# SCH_Small-keyboard_2024-08-15.net
KiCad netlist of a schematic drawn in EasyEDA
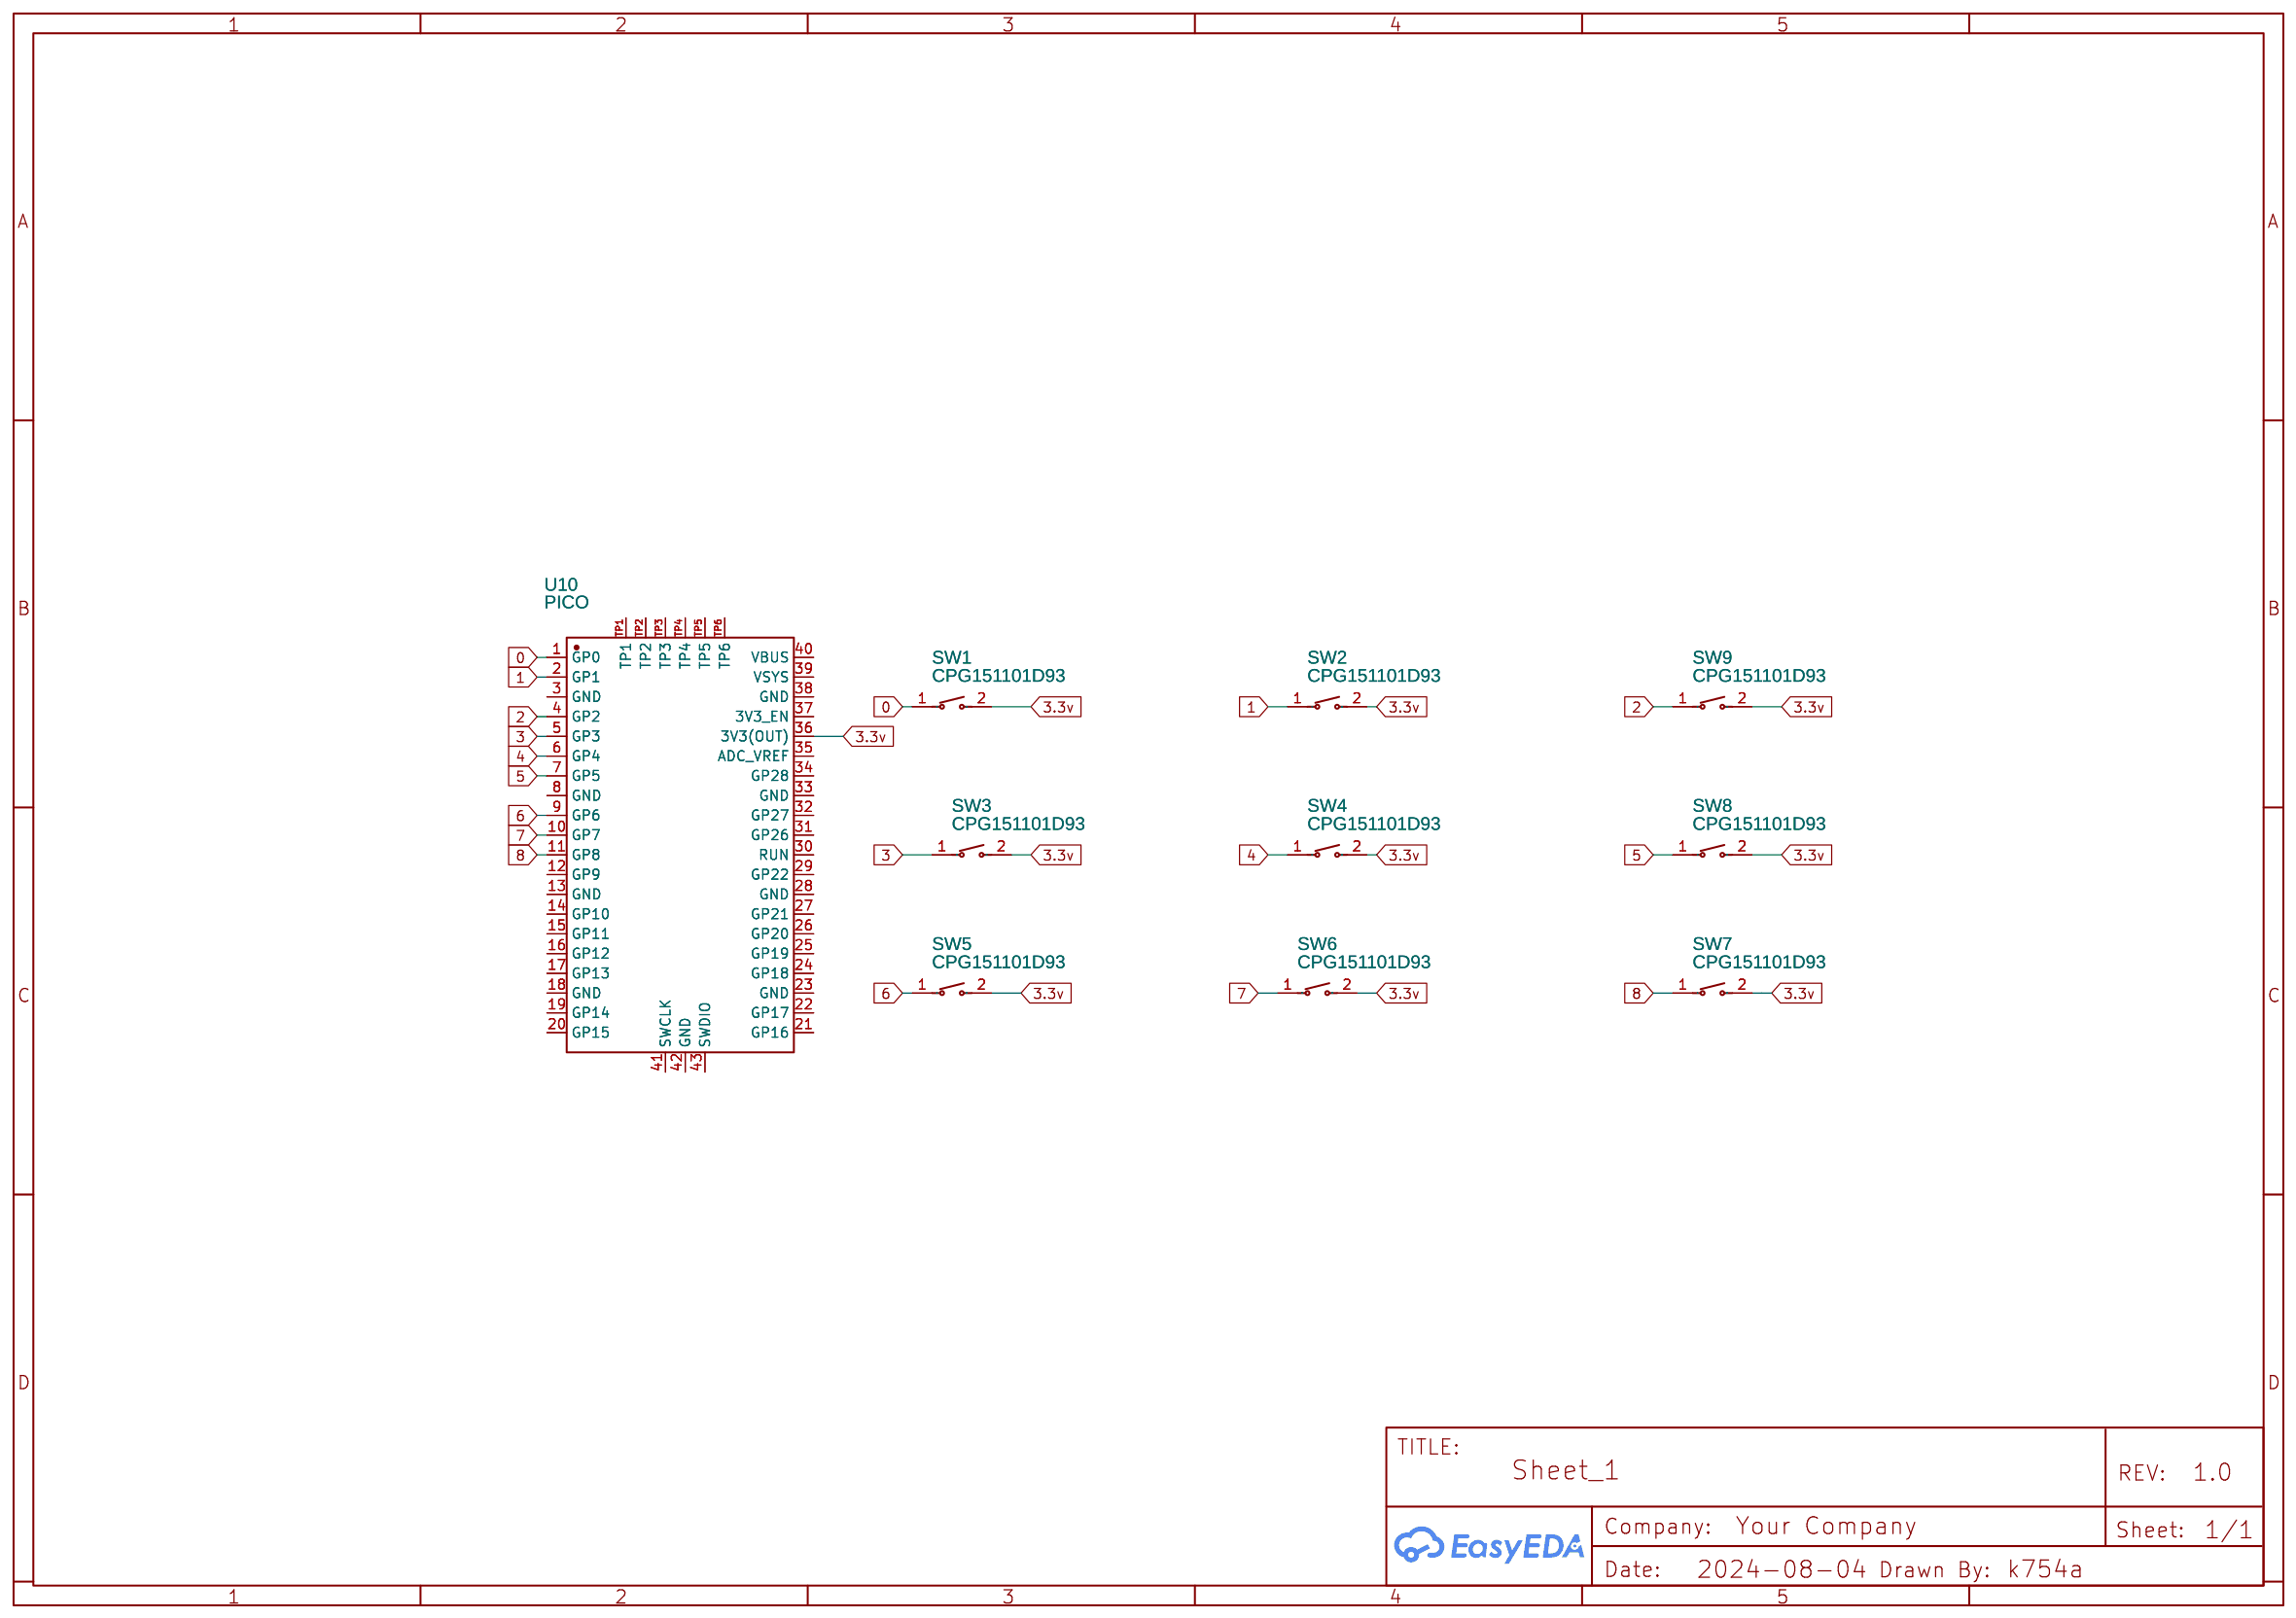
[diagram p0: schematic sheet]

(export (version "E")
  (design (tool "Eeschema 10.0.6"))
  (components
    (comp (ref "SW1")
      (value "CPG151101D93")
      (fields (field (name "Manufacturer") "Kailh(凯华)"))
      (libsource (lib "") (part "CPG151101D93"))
    )
    (comp (ref "SW2")
      (value "CPG151101D93")
      (fields (field (name "Manufacturer") "Kailh(凯华)"))
      (libsource (lib "") (part "CPG151101D93"))
    )
    (comp (ref "SW3")
      (value "CPG151101D93")
      (fields (field (name "Manufacturer") "Kailh(凯华)"))
      (libsource (lib "") (part "CPG151101D93"))
    )
    (comp (ref "SW4")
      (value "CPG151101D93")
      (fields (field (name "Manufacturer") "Kailh(凯华)"))
      (libsource (lib "") (part "CPG151101D93"))
    )
    (comp (ref "SW5")
      (value "CPG151101D93")
      (fields (field (name "Manufacturer") "Kailh(凯华)"))
      (libsource (lib "") (part "CPG151101D93"))
    )
    (comp (ref "SW6")
      (value "CPG151101D93")
      (fields (field (name "Manufacturer") "Kailh(凯华)"))
      (libsource (lib "") (part "CPG151101D93"))
    )
    (comp (ref "SW7")
      (value "CPG151101D93")
      (fields (field (name "Manufacturer") "Kailh(凯华)"))
      (libsource (lib "") (part "CPG151101D93"))
    )
    (comp (ref "SW8")
      (value "CPG151101D93")
      (fields (field (name "Manufacturer") "Kailh(凯华)"))
      (libsource (lib "") (part "CPG151101D93"))
    )
    (comp (ref "SW9")
      (value "CPG151101D93")
      (fields (field (name "Manufacturer") "Kailh(凯华)"))
      (libsource (lib "") (part "CPG151101D93"))
    )
    (comp (ref "U10")
      (value "PICO")
      (fields (field (name "Manufacturer") "Raspberry Pi(树莓派)"))
      (libsource (lib "") (part "PICO"))
    )
  )
  (nets
    (net (code "1") (name "0") (class "Default")
      (node (ref "SW1") (pin "1") (pinfunction "1_1") (pintype "unspecified"))
      (node (ref "U10") (pin "1") (pinfunction "GP0_1") (pintype "unspecified"))
    )
    (net (code "2") (name "1") (class "Default")
      (node (ref "SW2") (pin "1") (pinfunction "1_1") (pintype "unspecified"))
      (node (ref "U10") (pin "2") (pinfunction "GP1_2") (pintype "unspecified"))
    )
    (net (code "3") (name "2") (class "Default")
      (node (ref "SW9") (pin "1") (pinfunction "1_1") (pintype "unspecified"))
      (node (ref "U10") (pin "4") (pinfunction "GP2_4") (pintype "unspecified"))
    )
    (net (code "4") (name "3") (class "Default")
      (node (ref "SW3") (pin "1") (pinfunction "1_1") (pintype "unspecified"))
      (node (ref "U10") (pin "5") (pinfunction "GP3_5") (pintype "unspecified"))
    )
    (net (code "5") (name "3.3v") (class "Default")
      (node (ref "SW1") (pin "2") (pinfunction "2_2") (pintype "unspecified"))
      (node (ref "SW2") (pin "2") (pinfunction "2_2") (pintype "unspecified"))
      (node (ref "SW3") (pin "2") (pinfunction "2_2") (pintype "unspecified"))
      (node (ref "SW4") (pin "2") (pinfunction "2_2") (pintype "unspecified"))
      (node (ref "SW5") (pin "2") (pinfunction "2_2") (pintype "unspecified"))
      (node (ref "SW6") (pin "2") (pinfunction "2_2") (pintype "unspecified"))
      (node (ref "SW7") (pin "2") (pinfunction "2_2") (pintype "unspecified"))
      (node (ref "SW8") (pin "2") (pinfunction "2_2") (pintype "unspecified"))
      (node (ref "SW9") (pin "2") (pinfunction "2_2") (pintype "unspecified"))
      (node (ref "U10") (pin "36") (pinfunction "3V3(OUT)_36") (pintype "unspecified"))
    )
    (net (code "6") (name "4") (class "Default")
      (node (ref "SW4") (pin "1") (pinfunction "1_1") (pintype "unspecified"))
      (node (ref "U10") (pin "6") (pinfunction "GP4_6") (pintype "unspecified"))
    )
    (net (code "7") (name "5") (class "Default")
      (node (ref "SW8") (pin "1") (pinfunction "1_1") (pintype "unspecified"))
      (node (ref "U10") (pin "7") (pinfunction "GP5_7") (pintype "unspecified"))
    )
    (net (code "8") (name "6") (class "Default")
      (node (ref "SW5") (pin "1") (pinfunction "1_1") (pintype "unspecified"))
      (node (ref "U10") (pin "9") (pinfunction "GP6_9") (pintype "unspecified"))
    )
    (net (code "9") (name "7") (class "Default")
      (node (ref "SW6") (pin "1") (pinfunction "1_1") (pintype "unspecified"))
      (node (ref "U10") (pin "10") (pinfunction "GP7_10") (pintype "unspecified"))
    )
    (net (code "10") (name "8") (class "Default")
      (node (ref "SW7") (pin "1") (pinfunction "1_1") (pintype "unspecified"))
      (node (ref "U10") (pin "11") (pinfunction "GP8_11") (pintype "unspecified"))
    )
    (net (code "11") (name "unconnected-(U10-3V3_EN-Pad37)") (class "Default")
      (node (ref "U10") (pin "37") (pinfunction "3V3_EN_37") (pintype "unspecified"))
    )
    (net (code "12") (name "unconnected-(U10-ADC_VREF-Pad35)") (class "Default")
      (node (ref "U10") (pin "35") (pinfunction "ADC_VREF_35") (pintype "unspecified"))
    )
    (net (code "13") (name "unconnected-(U10-GND-Pad3)") (class "Default")
      (node (ref "U10") (pin "3") (pinfunction "GND_3") (pintype "unspecified"))
    )
    (net (code "14") (name "unconnected-(U10-GND-Pad8)") (class "Default")
      (node (ref "U10") (pin "8") (pinfunction "GND_8") (pintype "unspecified"))
    )
    (net (code "15") (name "unconnected-(U10-GND-Pad13)") (class "Default")
      (node (ref "U10") (pin "13") (pinfunction "GND_13") (pintype "unspecified"))
    )
    (net (code "16") (name "unconnected-(U10-GND-Pad18)") (class "Default")
      (node (ref "U10") (pin "18") (pinfunction "GND_18") (pintype "unspecified"))
    )
    (net (code "17") (name "unconnected-(U10-GND-Pad23)") (class "Default")
      (node (ref "U10") (pin "23") (pinfunction "GND_23") (pintype "unspecified"))
    )
    (net (code "18") (name "unconnected-(U10-GND-Pad28)") (class "Default")
      (node (ref "U10") (pin "28") (pinfunction "GND_28") (pintype "unspecified"))
    )
    (net (code "19") (name "unconnected-(U10-GND-Pad33)") (class "Default")
      (node (ref "U10") (pin "33") (pinfunction "GND_33") (pintype "unspecified"))
    )
    (net (code "20") (name "unconnected-(U10-GND-Pad38)") (class "Default")
      (node (ref "U10") (pin "38") (pinfunction "GND_38") (pintype "unspecified"))
    )
    (net (code "21") (name "unconnected-(U10-GND-Pad42)") (class "Default")
      (node (ref "U10") (pin "42") (pinfunction "GND_42") (pintype "unspecified"))
    )
    (net (code "22") (name "unconnected-(U10-GP9-Pad12)") (class "Default")
      (node (ref "U10") (pin "12") (pinfunction "GP9_12") (pintype "unspecified"))
    )
    (net (code "23") (name "unconnected-(U10-GP10-Pad14)") (class "Default")
      (node (ref "U10") (pin "14") (pinfunction "GP10_14") (pintype "unspecified"))
    )
    (net (code "24") (name "unconnected-(U10-GP11-Pad15)") (class "Default")
      (node (ref "U10") (pin "15") (pinfunction "GP11_15") (pintype "unspecified"))
    )
    (net (code "25") (name "unconnected-(U10-GP12-Pad16)") (class "Default")
      (node (ref "U10") (pin "16") (pinfunction "GP12_16") (pintype "unspecified"))
    )
    (net (code "26") (name "unconnected-(U10-GP13-Pad17)") (class "Default")
      (node (ref "U10") (pin "17") (pinfunction "GP13_17") (pintype "unspecified"))
    )
    (net (code "27") (name "unconnected-(U10-GP14-Pad19)") (class "Default")
      (node (ref "U10") (pin "19") (pinfunction "GP14_19") (pintype "unspecified"))
    )
    (net (code "28") (name "unconnected-(U10-GP15-Pad20)") (class "Default")
      (node (ref "U10") (pin "20") (pinfunction "GP15_20") (pintype "unspecified"))
    )
    (net (code "29") (name "unconnected-(U10-GP16-Pad21)") (class "Default")
      (node (ref "U10") (pin "21") (pinfunction "GP16_21") (pintype "unspecified"))
    )
    (net (code "30") (name "unconnected-(U10-GP17-Pad22)") (class "Default")
      (node (ref "U10") (pin "22") (pinfunction "GP17_22") (pintype "unspecified"))
    )
    (net (code "31") (name "unconnected-(U10-GP18-Pad24)") (class "Default")
      (node (ref "U10") (pin "24") (pinfunction "GP18_24") (pintype "unspecified"))
    )
    (net (code "32") (name "unconnected-(U10-GP19-Pad25)") (class "Default")
      (node (ref "U10") (pin "25") (pinfunction "GP19_25") (pintype "unspecified"))
    )
    (net (code "33") (name "unconnected-(U10-GP20-Pad26)") (class "Default")
      (node (ref "U10") (pin "26") (pinfunction "GP20_26") (pintype "unspecified"))
    )
    (net (code "34") (name "unconnected-(U10-GP21-Pad27)") (class "Default")
      (node (ref "U10") (pin "27") (pinfunction "GP21_27") (pintype "unspecified"))
    )
    (net (code "35") (name "unconnected-(U10-GP22-Pad29)") (class "Default")
      (node (ref "U10") (pin "29") (pinfunction "GP22_29") (pintype "unspecified"))
    )
    (net (code "36") (name "unconnected-(U10-GP26-Pad31)") (class "Default")
      (node (ref "U10") (pin "31") (pinfunction "GP26_31") (pintype "unspecified"))
    )
    (net (code "37") (name "unconnected-(U10-GP27-Pad32)") (class "Default")
      (node (ref "U10") (pin "32") (pinfunction "GP27_32") (pintype "unspecified"))
    )
    (net (code "38") (name "unconnected-(U10-GP28-Pad34)") (class "Default")
      (node (ref "U10") (pin "34") (pinfunction "GP28_34") (pintype "unspecified"))
    )
    (net (code "39") (name "unconnected-(U10-PadTP1)") (class "Default")
      (node (ref "U10") (pin "TP1") (pinfunction "TP1_TP1") (pintype "unspecified"))
    )
    (net (code "40") (name "unconnected-(U10-PadTP2)") (class "Default")
      (node (ref "U10") (pin "TP2") (pinfunction "TP2_TP2") (pintype "unspecified"))
    )
    (net (code "41") (name "unconnected-(U10-PadTP3)") (class "Default")
      (node (ref "U10") (pin "TP3") (pinfunction "TP3_TP3") (pintype "unspecified"))
    )
    (net (code "42") (name "unconnected-(U10-PadTP4)") (class "Default")
      (node (ref "U10") (pin "TP4") (pinfunction "TP4_TP4") (pintype "unspecified"))
    )
    (net (code "43") (name "unconnected-(U10-PadTP5)") (class "Default")
      (node (ref "U10") (pin "TP5") (pinfunction "TP5_TP5") (pintype "unspecified"))
    )
    (net (code "44") (name "unconnected-(U10-PadTP6)") (class "Default")
      (node (ref "U10") (pin "TP6") (pinfunction "TP6_TP6") (pintype "unspecified"))
    )
    (net (code "45") (name "unconnected-(U10-RUN-Pad30)") (class "Default")
      (node (ref "U10") (pin "30") (pinfunction "RUN_30") (pintype "unspecified"))
    )
    (net (code "46") (name "unconnected-(U10-SWCLK-Pad41)") (class "Default")
      (node (ref "U10") (pin "41") (pinfunction "SWCLK_41") (pintype "unspecified"))
    )
    (net (code "47") (name "unconnected-(U10-SWDIO-Pad43)") (class "Default")
      (node (ref "U10") (pin "43") (pinfunction "SWDIO_43") (pintype "unspecified"))
    )
    (net (code "48") (name "unconnected-(U10-VBUS-Pad40)") (class "Default")
      (node (ref "U10") (pin "40") (pinfunction "VBUS_40") (pintype "unspecified"))
    )
    (net (code "49") (name "unconnected-(U10-VSYS-Pad39)") (class "Default")
      (node (ref "U10") (pin "39") (pinfunction "VSYS_39") (pintype "unspecified"))
    )
  )
)
